# 150224_AriloRX_REV2_0_0_V2.net
KiCad netlist of a schematic drawn in EAGLE
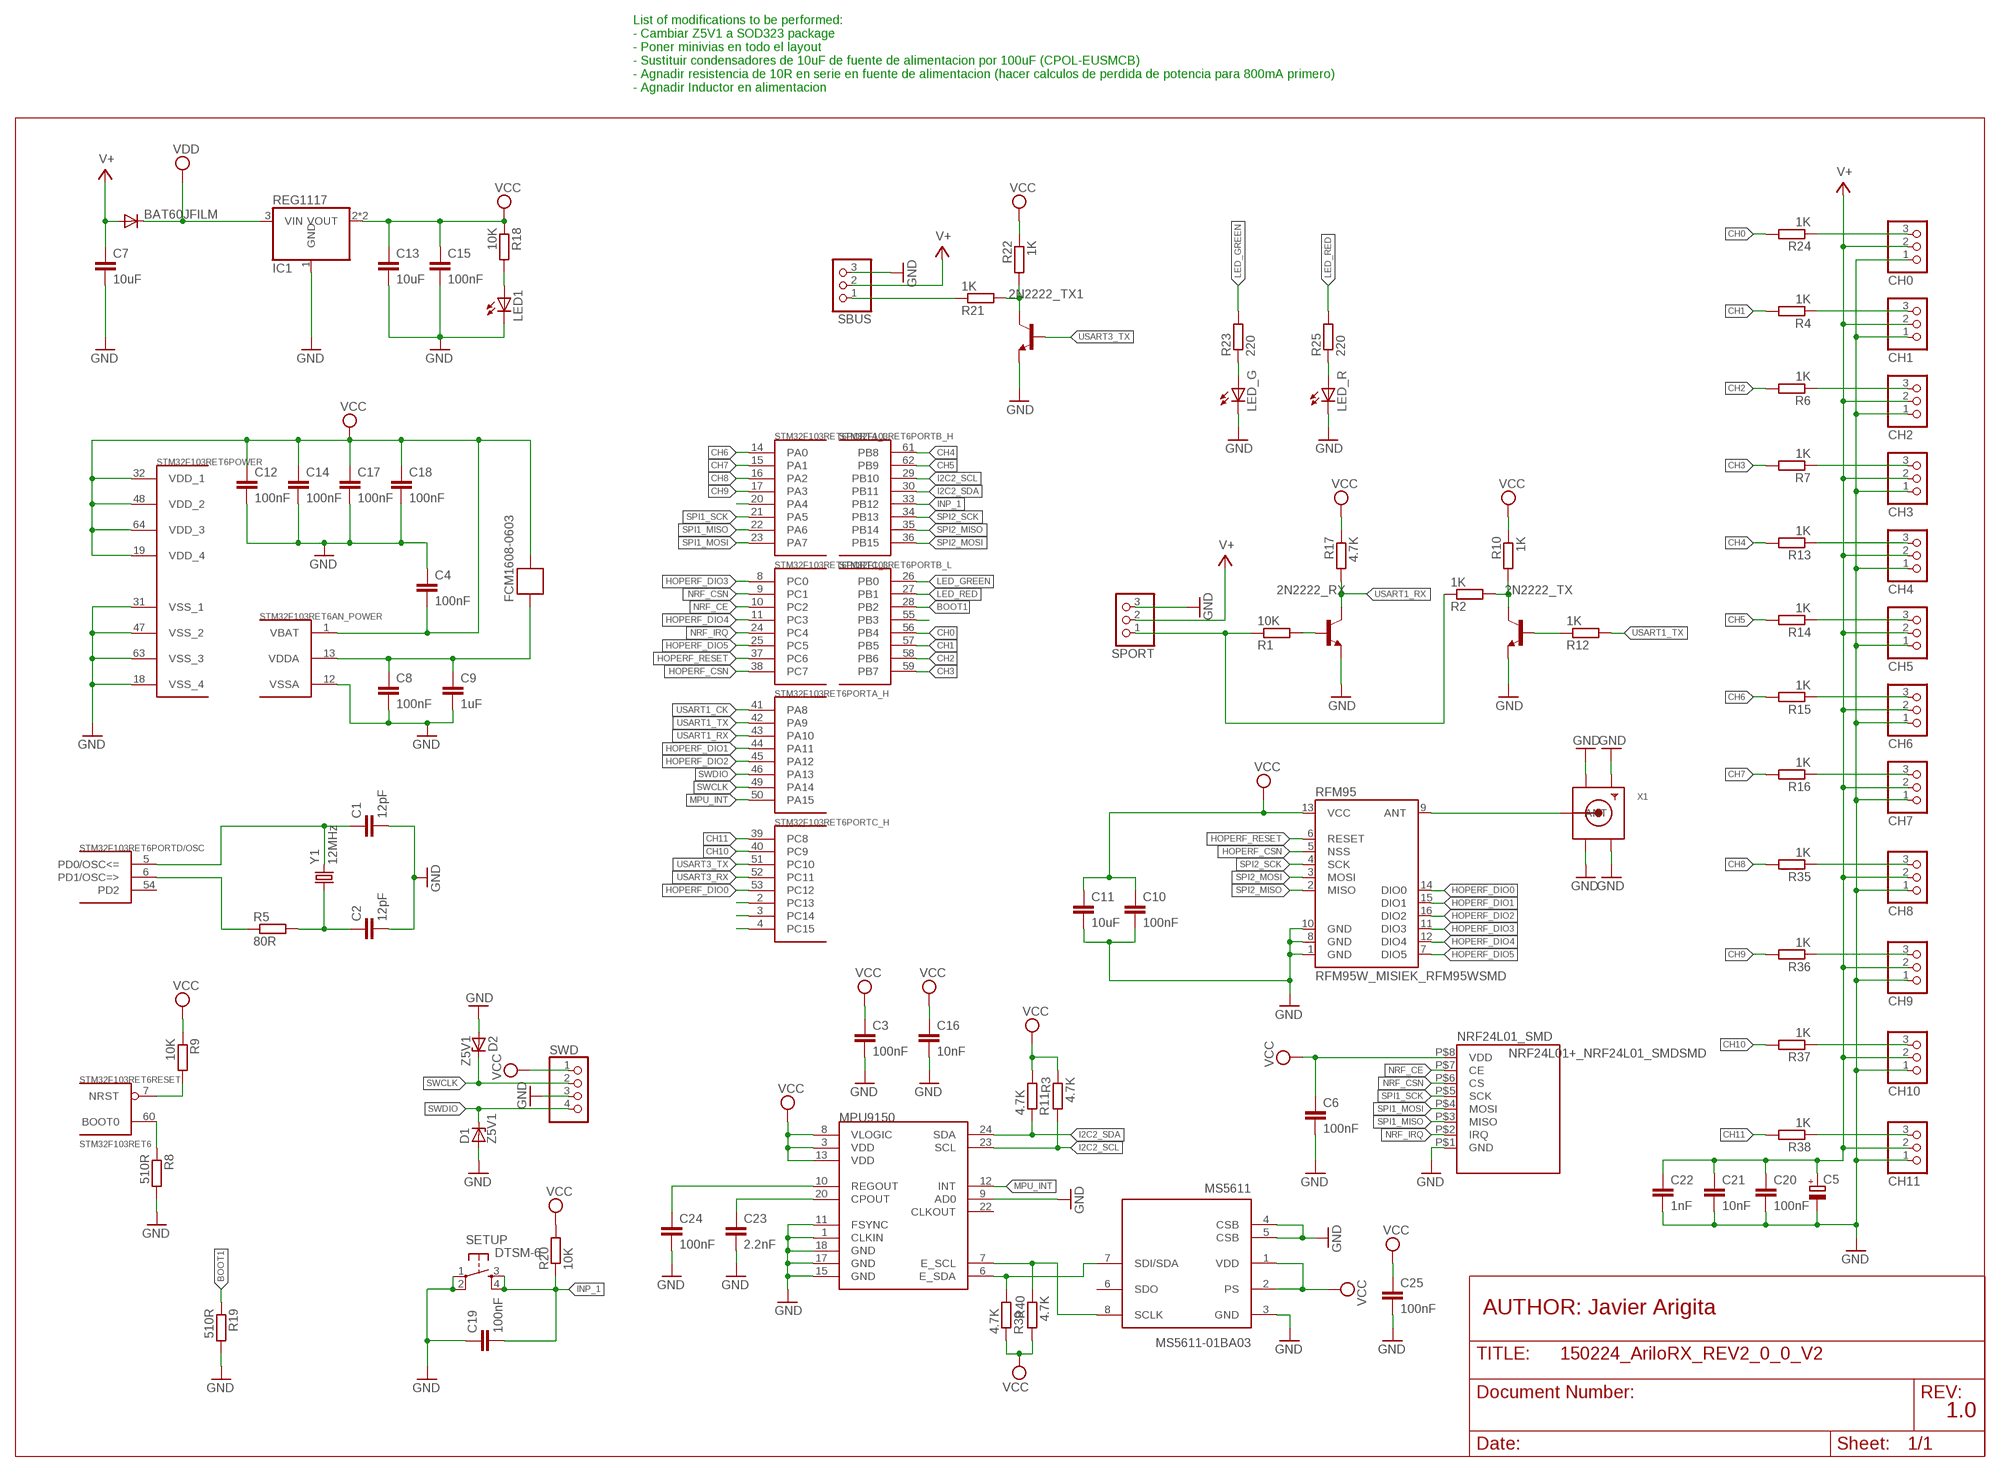
[diagram p0: schematic, sheet 1]

(export (version "E")
  (design (tool "Eeschema 10.0.6"))
  (components
    (comp (ref "2N2222_RX")
      (value "MMBT2222ALT1-NPN-SOT23-BEC")
      (footprint "eagle-import:SOT23-BEC")
      (libsource (lib "eagle-import") (part "-NPN-SOT23-BECMMBT2222ALT1"))
    )
    (comp (ref "2N2222_TX")
      (value "MMBT2222ALT1-NPN-SOT23-BEC")
      (footprint "eagle-import:SOT23-BEC")
      (libsource (lib "eagle-import") (part "-NPN-SOT23-BECMMBT2222ALT1"))
    )
    (comp (ref "2N2222_TX1")
      (value "MMBT2222ALT1-NPN-SOT23-BEC")
      (footprint "eagle-import:SOT23-BEC")
      (libsource (lib "eagle-import") (part "-NPN-SOT23-BECMMBT2222ALT1"))
    )
    (comp (ref "BAT60JFILM")
      (value "DIODE-SOD323-R")
      (footprint "eagle-import:SOD323-R")
      (libsource (lib "eagle-import") (part "DIODE-SOD323-R"))
    )
    (comp (ref "C1")
      (value "12pF")
      (footprint "eagle-import:RESISTOR_C0603")
      (libsource (lib "eagle-import") (part "RESISTOR_C-EUC0603"))
    )
    (comp (ref "C2")
      (value "12pF")
      (footprint "eagle-import:RESISTOR_C0603")
      (libsource (lib "eagle-import") (part "RESISTOR_C-EUC0603"))
    )
    (comp (ref "C3")
      (value "100nF")
      (footprint "eagle-import:RESISTOR_C0603")
      (libsource (lib "eagle-import") (part "RESISTOR_C-EUC0603"))
    )
    (comp (ref "C4")
      (value "100nF")
      (footprint "eagle-import:RESISTOR_C0603")
      (libsource (lib "eagle-import") (part "RESISTOR_C-EUC0603"))
    )
    (comp (ref "C5")
      (value "CPOL-EUSMCB")
      (footprint "eagle-import:SMC_B")
      (libsource (lib "eagle-import") (part "CPOL-EUSMCB"))
    )
    (comp (ref "C6")
      (value "100nF")
      (footprint "eagle-import:RESISTOR_C0603")
      (libsource (lib "eagle-import") (part "RESISTOR_C-EUC0603"))
    )
    (comp (ref "C7")
      (value "10uF")
      (footprint "eagle-import:RESISTOR_C3216")
      (libsource (lib "eagle-import") (part "RESISTOR_C-EUC3216"))
    )
    (comp (ref "C8")
      (value "100nF")
      (footprint "eagle-import:RESISTOR_C0603")
      (libsource (lib "eagle-import") (part "RESISTOR_C-EUC0603"))
    )
    (comp (ref "C9")
      (value "1uF")
      (footprint "eagle-import:RESISTOR_C0603")
      (libsource (lib "eagle-import") (part "RESISTOR_C-EUC0603"))
    )
    (comp (ref "C10")
      (value "100nF")
      (footprint "eagle-import:RESISTOR_C0603")
      (libsource (lib "eagle-import") (part "RESISTOR_C-EUC0603"))
    )
    (comp (ref "C11")
      (value "10uF")
      (footprint "eagle-import:RESISTOR_C3216")
      (libsource (lib "eagle-import") (part "RESISTOR_C-EUC3216"))
    )
    (comp (ref "C12")
      (value "100nF")
      (footprint "eagle-import:RESISTOR_C0603")
      (libsource (lib "eagle-import") (part "RESISTOR_C-EUC0603"))
    )
    (comp (ref "C13")
      (value "10uF")
      (footprint "eagle-import:RESISTOR_C3216")
      (libsource (lib "eagle-import") (part "RESISTOR_C-EUC3216"))
    )
    (comp (ref "C14")
      (value "100nF")
      (footprint "eagle-import:RESISTOR_C0603")
      (libsource (lib "eagle-import") (part "RESISTOR_C-EUC0603"))
    )
    (comp (ref "C15")
      (value "100nF")
      (footprint "eagle-import:RESISTOR_C0603")
      (libsource (lib "eagle-import") (part "RESISTOR_C-EUC0603"))
    )
    (comp (ref "C16")
      (value "10nF")
      (footprint "eagle-import:RESISTOR_C0603")
      (libsource (lib "eagle-import") (part "RESISTOR_C-EUC0603"))
    )
    (comp (ref "C17")
      (value "100nF")
      (footprint "eagle-import:RESISTOR_C0603")
      (libsource (lib "eagle-import") (part "RESISTOR_C-EUC0603"))
    )
    (comp (ref "C18")
      (value "100nF")
      (footprint "eagle-import:RESISTOR_C0603")
      (libsource (lib "eagle-import") (part "RESISTOR_C-EUC0603"))
    )
    (comp (ref "C19")
      (value "100nF")
      (footprint "eagle-import:RESISTOR_C0603")
      (libsource (lib "eagle-import") (part "RESISTOR_C-EUC0603"))
    )
    (comp (ref "C20")
      (value "100nF")
      (footprint "eagle-import:RESISTOR_C0603")
      (libsource (lib "eagle-import") (part "RESISTOR_C-EUC0603"))
    )
    (comp (ref "C21")
      (value "10nF")
      (footprint "eagle-import:RESISTOR_C0603")
      (libsource (lib "eagle-import") (part "RESISTOR_C-EUC0603"))
    )
    (comp (ref "C22")
      (value "1nF")
      (footprint "eagle-import:RESISTOR_C0603")
      (libsource (lib "eagle-import") (part "RESISTOR_C-EUC0603"))
    )
    (comp (ref "C23")
      (value "2.2nF")
      (footprint "eagle-import:RESISTOR_C0603")
      (libsource (lib "eagle-import") (part "RESISTOR_C-EUC0603"))
    )
    (comp (ref "C24")
      (value "100nF")
      (footprint "eagle-import:RESISTOR_C0603")
      (libsource (lib "eagle-import") (part "RESISTOR_C-EUC0603"))
    )
    (comp (ref "C25")
      (value "100nF")
      (footprint "eagle-import:RESISTOR_C0603")
      (libsource (lib "eagle-import") (part "RESISTOR_C-EUC0603"))
    )
    (comp (ref "CH0")
      (value "PINHD-1X3")
      (footprint "eagle-import:1X03")
      (libsource (lib "eagle-import") (part "PINHD-1X3"))
    )
    (comp (ref "CH1")
      (value "PINHD-1X3")
      (footprint "eagle-import:1X03")
      (libsource (lib "eagle-import") (part "PINHD-1X3"))
    )
    (comp (ref "CH2")
      (value "PINHD-1X3")
      (footprint "eagle-import:1X03")
      (libsource (lib "eagle-import") (part "PINHD-1X3"))
    )
    (comp (ref "CH3")
      (value "PINHD-1X3")
      (footprint "eagle-import:1X03")
      (libsource (lib "eagle-import") (part "PINHD-1X3"))
    )
    (comp (ref "CH4")
      (value "PINHD-1X3")
      (footprint "eagle-import:1X03")
      (libsource (lib "eagle-import") (part "PINHD-1X3"))
    )
    (comp (ref "CH5")
      (value "PINHD-1X3")
      (footprint "eagle-import:1X03")
      (libsource (lib "eagle-import") (part "PINHD-1X3"))
    )
    (comp (ref "CH6")
      (value "PINHD-1X3")
      (footprint "eagle-import:1X03")
      (libsource (lib "eagle-import") (part "PINHD-1X3"))
    )
    (comp (ref "CH7")
      (value "PINHD-1X3")
      (footprint "eagle-import:1X03")
      (libsource (lib "eagle-import") (part "PINHD-1X3"))
    )
    (comp (ref "CH8")
      (value "PINHD-1X3")
      (footprint "eagle-import:1X03")
      (libsource (lib "eagle-import") (part "PINHD-1X3"))
    )
    (comp (ref "CH9")
      (value "PINHD-1X3")
      (footprint "eagle-import:1X03")
      (libsource (lib "eagle-import") (part "PINHD-1X3"))
    )
    (comp (ref "CH10")
      (value "PINHD-1X3")
      (footprint "eagle-import:1X03")
      (libsource (lib "eagle-import") (part "PINHD-1X3"))
    )
    (comp (ref "CH11")
      (value "PINHD-1X3")
      (footprint "eagle-import:1X03")
      (libsource (lib "eagle-import") (part "PINHD-1X3"))
    )
    (comp (ref "D1")
      (value "Z5V1")
      (footprint "eagle-import:SOD80C")
      (libsource (lib "eagle-import") (part "ZENER-DIODESOD80C"))
    )
    (comp (ref "D2")
      (value "Z5V1")
      (footprint "eagle-import:SOD80C")
      (libsource (lib "eagle-import") (part "ZENER-DIODESOD80C"))
    )
    (comp (ref "FCM1608-0603")
      (value "FERRITE-BEAD")
      (footprint "eagle-import:R0603")
      (libsource (lib "eagle-import") (part "FERRITE-BEAD"))
    )
    (comp (ref "IC1")
      (value "REG1117")
      (footprint "eagle-import:SOT223")
      (libsource (lib "eagle-import") (part "REG1117"))
    )
    (comp (ref "LED1")
      (value "LED_LEDCHIP-LED0603")
      (footprint "eagle-import:LED_CHIP-LED0603")
      (libsource (lib "eagle-import") (part "LED_LEDCHIP-LED0603"))
    )
    (comp (ref "LED_G")
      (value "LEDCHIP-LED0603")
      (footprint "eagle-import:CHIP-LED0603")
      (libsource (lib "eagle-import") (part "LEDCHIP-LED0603"))
    )
    (comp (ref "LED_R")
      (value "LEDCHIP-LED0603")
      (footprint "eagle-import:CHIP-LED0603")
      (libsource (lib "eagle-import") (part "LEDCHIP-LED0603"))
    )
    (comp (ref "MPU9150")
      (value "MPU-9150QFN-24-NP")
      (footprint "eagle-import:QFN-24-NP")
      (libsource (lib "eagle-import") (part "MPU-9150QFN-24-NP"))
    )
    (comp (ref "MS5611")
      (value "MS5611-01BA03")
      (footprint "eagle-import:SON125P300X500X100-8N")
      (libsource (lib "eagle-import") (part "MS5611-01BA03"))
    )
    (comp (ref "NRF24L01_SMD")
      (value "NRF24L01+_NRF24L01_SMDSMD")
      (footprint "eagle-import:NRF24L01+_NRF24L01_SMD")
      (libsource (lib "eagle-import") (part "NRF24L01+_NRF24L01_SMDSMD"))
    )
    (comp (ref "R1")
      (value "10K")
      (footprint "eagle-import:RCL_R0603")
      (libsource (lib "eagle-import") (part "RCL_R-EU_R0603"))
    )
    (comp (ref "R2")
      (value "1K")
      (footprint "eagle-import:RCL_R0603")
      (libsource (lib "eagle-import") (part "RCL_R-EU_R0603"))
    )
    (comp (ref "R3")
      (value "4.7K")
      (footprint "eagle-import:RCL_R0603")
      (libsource (lib "eagle-import") (part "RCL_R-EU_R0603"))
    )
    (comp (ref "R4")
      (value "1K")
      (footprint "eagle-import:RCL_R0603")
      (libsource (lib "eagle-import") (part "RCL_R-EU_R0603"))
    )
    (comp (ref "R5")
      (value "80R")
      (footprint "eagle-import:RCL_R0603")
      (libsource (lib "eagle-import") (part "RCL_R-EU_R0603"))
    )
    (comp (ref "R6")
      (value "1K")
      (footprint "eagle-import:RCL_R0603")
      (libsource (lib "eagle-import") (part "RCL_R-EU_R0603"))
    )
    (comp (ref "R7")
      (value "1K")
      (footprint "eagle-import:RCL_R0603")
      (libsource (lib "eagle-import") (part "RCL_R-EU_R0603"))
    )
    (comp (ref "R8")
      (value "510R")
      (footprint "eagle-import:RCL_R0603")
      (libsource (lib "eagle-import") (part "RCL_R-EU_R0603"))
    )
    (comp (ref "R9")
      (value "10K")
      (footprint "eagle-import:RCL_R0603")
      (libsource (lib "eagle-import") (part "RCL_R-EU_R0603"))
    )
    (comp (ref "R10")
      (value "1K")
      (footprint "eagle-import:RCL_R0603")
      (libsource (lib "eagle-import") (part "RCL_R-EU_R0603"))
    )
    (comp (ref "R11")
      (value "4.7K")
      (footprint "eagle-import:RCL_R0603")
      (libsource (lib "eagle-import") (part "RCL_R-EU_R0603"))
    )
    (comp (ref "R12")
      (value "1K")
      (footprint "eagle-import:RCL_R0603")
      (libsource (lib "eagle-import") (part "RCL_R-EU_R0603"))
    )
    (comp (ref "R13")
      (value "1K")
      (footprint "eagle-import:RCL_R0603")
      (libsource (lib "eagle-import") (part "RCL_R-EU_R0603"))
    )
    (comp (ref "R14")
      (value "1K")
      (footprint "eagle-import:RCL_R0603")
      (libsource (lib "eagle-import") (part "RCL_R-EU_R0603"))
    )
    (comp (ref "R15")
      (value "1K")
      (footprint "eagle-import:RCL_R0603")
      (libsource (lib "eagle-import") (part "RCL_R-EU_R0603"))
    )
    (comp (ref "R16")
      (value "1K")
      (footprint "eagle-import:RCL_R0603")
      (libsource (lib "eagle-import") (part "RCL_R-EU_R0603"))
    )
    (comp (ref "R17")
      (value "4.7K")
      (footprint "eagle-import:RCL_R0603")
      (libsource (lib "eagle-import") (part "RCL_R-EU_R0603"))
    )
    (comp (ref "R18")
      (value "10K")
      (footprint "eagle-import:RCL_R0603")
      (libsource (lib "eagle-import") (part "RCL_R-EU_R0603"))
    )
    (comp (ref "R19")
      (value "510R")
      (footprint "eagle-import:RCL_R0603")
      (libsource (lib "eagle-import") (part "RCL_R-EU_R0603"))
    )
    (comp (ref "R20")
      (value "10K")
      (footprint "eagle-import:RCL_R0603")
      (libsource (lib "eagle-import") (part "RCL_R-EU_R0603"))
    )
    (comp (ref "R21")
      (value "1K")
      (footprint "eagle-import:RCL_R0603")
      (libsource (lib "eagle-import") (part "RCL_R-EU_R0603"))
    )
    (comp (ref "R22")
      (value "1K")
      (footprint "eagle-import:RCL_R0603")
      (libsource (lib "eagle-import") (part "RCL_R-EU_R0603"))
    )
    (comp (ref "R23")
      (value "220")
      (footprint "eagle-import:RCL_R0603")
      (libsource (lib "eagle-import") (part "RCL_R-EU_R0603"))
    )
    (comp (ref "R24")
      (value "1K")
      (footprint "eagle-import:RCL_R0603")
      (libsource (lib "eagle-import") (part "RCL_R-EU_R0603"))
    )
    (comp (ref "R25")
      (value "220")
      (footprint "eagle-import:RCL_R0603")
      (libsource (lib "eagle-import") (part "RCL_R-EU_R0603"))
    )
    (comp (ref "R35")
      (value "1K")
      (footprint "eagle-import:RCL_R0603")
      (libsource (lib "eagle-import") (part "RCL_R-EU_R0603"))
    )
    (comp (ref "R36")
      (value "1K")
      (footprint "eagle-import:RCL_R0603")
      (libsource (lib "eagle-import") (part "RCL_R-EU_R0603"))
    )
    (comp (ref "R37")
      (value "1K")
      (footprint "eagle-import:RCL_R0603")
      (libsource (lib "eagle-import") (part "RCL_R-EU_R0603"))
    )
    (comp (ref "R38")
      (value "1K")
      (footprint "eagle-import:RCL_R0603")
      (libsource (lib "eagle-import") (part "RCL_R-EU_R0603"))
    )
    (comp (ref "R39")
      (value "4.7K")
      (footprint "eagle-import:RCL_R0603")
      (libsource (lib "eagle-import") (part "RCL_R-EU_R0603"))
    )
    (comp (ref "R40")
      (value "4.7K")
      (footprint "eagle-import:RCL_R0603")
      (libsource (lib "eagle-import") (part "RCL_R-EU_R0603"))
    )
    (comp (ref "RFM95")
      (value "RFM95W_MISIEK_RFM95WSMD")
      (footprint "eagle-import:RFM95W_MISIEK_RFM95W_SMD")
      (libsource (lib "eagle-import") (part "RFM95W_MISIEK_RFM95WSMD"))
    )
    (comp (ref "SBUS")
      (value "PINHD-1X3")
      (footprint "eagle-import:1X03")
      (libsource (lib "eagle-import") (part "PINHD-1X3"))
    )
    (comp (ref "SETUP")
      (value "DTSM-6")
      (footprint "eagle-import:DTSM-6")
      (libsource (lib "eagle-import") (part "DTSM-6"))
    )
    (comp (ref "SPORT")
      (value "PINHD-1X3")
      (footprint "eagle-import:1X03")
      (libsource (lib "eagle-import") (part "PINHD-1X3"))
    )
    (comp (ref "STM32F103RET6")
      (value "STM32F103RET6")
      (footprint "eagle-import:TQFP64")
      (libsource (lib "eagle-import") (part "STM32F10XRXT6"))
    )
    (comp (ref "SWD")
      (value "PINHD-1X4")
      (footprint "eagle-import:1X04")
      (libsource (lib "eagle-import") (part "PINHD-1X4"))
    )
    (comp (ref "X1")
      (value "SMACONNECTOR_EDGE")
      (footprint "eagle-import:SMA_EDGELAUNCH")
      (libsource (lib "eagle-import") (part "SMACONNECTOR_EDGE"))
    )
    (comp (ref "Y1")
      (value "12MHz")
      (footprint "eagle-import:CRYSTAL-SMD-5X3")
      (libsource (lib "eagle-import") (part "CRYSTAL5X3"))
    )
  )
  (nets
    (net (code "1") (name "BOOT1") (class "Default")
      (node (ref "R19") (pin "1") (pinfunction "1_1") (pintype "passive"))
      (node (ref "STM32F103RET6") (pin "28") (pinfunction "PB2_28") (pintype "bidirectional"))
    )
    (net (code "2") (name "CH0") (class "Default")
      (node (ref "R24") (pin "2") (pinfunction "2_2") (pintype "passive"))
      (node (ref "STM32F103RET6") (pin "56") (pinfunction "PB4_56") (pintype "bidirectional"))
    )
    (net (code "3") (name "CH1") (class "Default")
      (node (ref "R4") (pin "2") (pinfunction "2_2") (pintype "passive"))
      (node (ref "STM32F103RET6") (pin "57") (pinfunction "PB5_57") (pintype "bidirectional"))
    )
    (net (code "4") (name "CH2") (class "Default")
      (node (ref "R6") (pin "2") (pinfunction "2_2") (pintype "passive"))
      (node (ref "STM32F103RET6") (pin "58") (pinfunction "PB6_58") (pintype "bidirectional"))
    )
    (net (code "5") (name "CH3") (class "Default")
      (node (ref "R7") (pin "2") (pinfunction "2_2") (pintype "passive"))
      (node (ref "STM32F103RET6") (pin "59") (pinfunction "PB7_59") (pintype "bidirectional"))
    )
    (net (code "6") (name "CH4") (class "Default")
      (node (ref "R13") (pin "2") (pinfunction "2_2") (pintype "passive"))
      (node (ref "STM32F103RET6") (pin "61") (pinfunction "PB8_61") (pintype "bidirectional"))
    )
    (net (code "7") (name "CH5") (class "Default")
      (node (ref "R14") (pin "2") (pinfunction "2_2") (pintype "passive"))
      (node (ref "STM32F103RET6") (pin "62") (pinfunction "PB9_62") (pintype "bidirectional"))
    )
    (net (code "8") (name "CH6") (class "Default")
      (node (ref "R15") (pin "2") (pinfunction "2_2") (pintype "passive"))
      (node (ref "STM32F103RET6") (pin "14") (pinfunction "PA0_14") (pintype "bidirectional"))
    )
    (net (code "9") (name "CH7") (class "Default")
      (node (ref "R16") (pin "2") (pinfunction "2_2") (pintype "passive"))
      (node (ref "STM32F103RET6") (pin "15") (pinfunction "PA1_15") (pintype "bidirectional"))
    )
    (net (code "10") (name "CH8") (class "Default")
      (node (ref "R35") (pin "2") (pinfunction "2_2") (pintype "passive"))
      (node (ref "STM32F103RET6") (pin "16") (pinfunction "PA2_16") (pintype "bidirectional"))
    )
    (net (code "11") (name "CH9") (class "Default")
      (node (ref "R36") (pin "2") (pinfunction "2_2") (pintype "passive"))
      (node (ref "STM32F103RET6") (pin "17") (pinfunction "PA3_17") (pintype "bidirectional"))
    )
    (net (code "12") (name "CH10") (class "Default")
      (node (ref "R37") (pin "2") (pinfunction "2_2") (pintype "passive"))
      (node (ref "STM32F103RET6") (pin "40") (pinfunction "PC9_40") (pintype "bidirectional"))
    )
    (net (code "13") (name "CH11") (class "Default")
      (node (ref "R38") (pin "2") (pinfunction "2_2") (pintype "passive"))
      (node (ref "STM32F103RET6") (pin "39") (pinfunction "PC8_39") (pintype "bidirectional"))
    )
    (net (code "14") (name "GND") (class "Default")
      (node (ref "2N2222_RX") (pin "E") (pinfunction "E_E") (pintype "passive"))
      (node (ref "2N2222_TX") (pin "E") (pinfunction "E_E") (pintype "passive"))
      (node (ref "2N2222_TX1") (pin "E") (pinfunction "E_E") (pintype "passive"))
      (node (ref "C1") (pin "2") (pinfunction "2_2") (pintype "passive"))
      (node (ref "C10") (pin "2") (pinfunction "2_2") (pintype "passive"))
      (node (ref "C11") (pin "2") (pinfunction "2_2") (pintype "passive"))
      (node (ref "C12") (pin "2") (pinfunction "2_2") (pintype "passive"))
      (node (ref "C13") (pin "2") (pinfunction "2_2") (pintype "passive"))
      (node (ref "C14") (pin "2") (pinfunction "2_2") (pintype "passive"))
      (node (ref "C15") (pin "2") (pinfunction "2_2") (pintype "passive"))
      (node (ref "C16") (pin "2") (pinfunction "2_2") (pintype "passive"))
      (node (ref "C17") (pin "2") (pinfunction "2_2") (pintype "passive"))
      (node (ref "C18") (pin "2") (pinfunction "2_2") (pintype "passive"))
      (node (ref "C19") (pin "1") (pinfunction "1_1") (pintype "passive"))
      (node (ref "C2") (pin "2") (pinfunction "2_2") (pintype "passive"))
      (node (ref "C20") (pin "2") (pinfunction "2_2") (pintype "passive"))
      (node (ref "C21") (pin "2") (pinfunction "2_2") (pintype "passive"))
      (node (ref "C22") (pin "2") (pinfunction "2_2") (pintype "passive"))
      (node (ref "C23") (pin "2") (pinfunction "2_2") (pintype "passive"))
      (node (ref "C24") (pin "2") (pinfunction "2_2") (pintype "passive"))
      (node (ref "C25") (pin "2") (pinfunction "2_2") (pintype "passive"))
      (node (ref "C3") (pin "2") (pinfunction "2_2") (pintype "passive"))
      (node (ref "C4") (pin "1") (pinfunction "1_1") (pintype "passive"))
      (node (ref "C5") (pin "-") (pinfunction "-_-") (pintype "passive"))
      (node (ref "C6") (pin "2") (pinfunction "2_2") (pintype "passive"))
      (node (ref "C7") (pin "2") (pinfunction "2_2") (pintype "passive"))
      (node (ref "C8") (pin "2") (pinfunction "2_2") (pintype "passive"))
      (node (ref "C9") (pin "2") (pinfunction "2_2") (pintype "passive"))
      (node (ref "CH0") (pin "1") (pinfunction "1_1") (pintype "passive"))
      (node (ref "CH1") (pin "1") (pinfunction "1_1") (pintype "passive"))
      (node (ref "CH10") (pin "1") (pinfunction "1_1") (pintype "passive"))
      (node (ref "CH11") (pin "1") (pinfunction "1_1") (pintype "passive"))
      (node (ref "CH2") (pin "1") (pinfunction "1_1") (pintype "passive"))
      (node (ref "CH3") (pin "1") (pinfunction "1_1") (pintype "passive"))
      (node (ref "CH4") (pin "1") (pinfunction "1_1") (pintype "passive"))
      (node (ref "CH5") (pin "1") (pinfunction "1_1") (pintype "passive"))
      (node (ref "CH6") (pin "1") (pinfunction "1_1") (pintype "passive"))
      (node (ref "CH7") (pin "1") (pinfunction "1_1") (pintype "passive"))
      (node (ref "CH8") (pin "1") (pinfunction "1_1") (pintype "passive"))
      (node (ref "CH9") (pin "1") (pinfunction "1_1") (pintype "passive"))
      (node (ref "D1") (pin "A") (pinfunction "A_A") (pintype "passive"))
      (node (ref "D2") (pin "A") (pinfunction "A_A") (pintype "passive"))
      (node (ref "IC1") (pin "1") (pinfunction "GND_1") (pintype "power_in"))
      (node (ref "LED1") (pin "C") (pinfunction "C_C") (pintype "passive"))
      (node (ref "LED_G") (pin "C") (pinfunction "C_C") (pintype "passive"))
      (node (ref "LED_R") (pin "C") (pinfunction "C_C") (pintype "passive"))
      (node (ref "MPU9150") (pin "1") (pinfunction "CLKIN_1") (pintype "bidirectional"))
      (node (ref "MPU9150") (pin "11") (pinfunction "FSYNC_11") (pintype "bidirectional"))
      (node (ref "MPU9150") (pin "15") (pinfunction "GND_15") (pintype "bidirectional"))
      (node (ref "MPU9150") (pin "17") (pinfunction "GND_17") (pintype "bidirectional"))
      (node (ref "MPU9150") (pin "18") (pinfunction "GND_18") (pintype "bidirectional"))
      (node (ref "MPU9150") (pin "9") (pinfunction "AD0_9") (pintype "bidirectional"))
      (node (ref "MS5611") (pin "3") (pinfunction "GND_3") (pintype "power_in"))
      (node (ref "MS5611") (pin "4") (pinfunction "CSB_4") (pintype "input"))
      (node (ref "MS5611") (pin "5") (pinfunction "CSB_5") (pintype "input"))
      (node (ref "NRF24L01_SMD") (pin "P$1") (pinfunction "GND_P$1") (pintype "power_in"))
      (node (ref "R19") (pin "2") (pinfunction "2_2") (pintype "passive"))
      (node (ref "R8") (pin "2") (pinfunction "2_2") (pintype "passive"))
      (node (ref "RFM95") (pin "1") (pinfunction "GND_1") (pintype "power_in"))
      (node (ref "RFM95") (pin "10") (pinfunction "GND_10") (pintype "power_in"))
      (node (ref "RFM95") (pin "8") (pinfunction "GND_8") (pintype "power_in"))
      (node (ref "SBUS") (pin "3") (pinfunction "3_3") (pintype "passive"))
      (node (ref "SETUP") (pin "1") (pinfunction "1_1") (pintype "passive"))
      (node (ref "SETUP") (pin "2") (pinfunction "2_2") (pintype "passive"))
      (node (ref "SPORT") (pin "3") (pinfunction "3_3") (pintype "passive"))
      (node (ref "STM32F103RET6") (pin "12") (pinfunction "VSSA_12") (pintype "power_in"))
      (node (ref "STM32F103RET6") (pin "18") (pinfunction "VSS_4_18") (pintype "power_in"))
      (node (ref "STM32F103RET6") (pin "31") (pinfunction "VSS_1_31") (pintype "power_in"))
      (node (ref "STM32F103RET6") (pin "47") (pinfunction "VSS_2_47") (pintype "power_in"))
      (node (ref "STM32F103RET6") (pin "63") (pinfunction "VSS_3_63") (pintype "power_in"))
      (node (ref "SWD") (pin "3") (pinfunction "3_3") (pintype "passive"))
      (node (ref "X1") (pin "GND@1") (pinfunction "GND4_GND@1") (pintype "power_in"))
      (node (ref "X1") (pin "GND@2") (pinfunction "GND3_GND@2") (pintype "power_in"))
      (node (ref "X1") (pin "GND@3") (pinfunction "GND2_GND@3") (pintype "power_in"))
      (node (ref "X1") (pin "GND@4") (pinfunction "GND1_GND@4") (pintype "power_in"))
    )
    (net (code "15") (name "HOPERF_CSN") (class "Default")
      (node (ref "RFM95") (pin "5") (pinfunction "NSS_5") (pintype "input"))
      (node (ref "STM32F103RET6") (pin "38") (pinfunction "PC7_38") (pintype "bidirectional"))
    )
    (net (code "16") (name "HOPERF_DIO0") (class "Default")
      (node (ref "RFM95") (pin "14") (pinfunction "DIO0_14") (pintype "input"))
      (node (ref "STM32F103RET6") (pin "53") (pinfunction "PC12_53") (pintype "bidirectional"))
    )
    (net (code "17") (name "HOPERF_DIO1") (class "Default")
      (node (ref "RFM95") (pin "15") (pinfunction "DIO1_15") (pintype "input"))
      (node (ref "STM32F103RET6") (pin "44") (pinfunction "PA11_44") (pintype "bidirectional"))
    )
    (net (code "18") (name "HOPERF_DIO2") (class "Default")
      (node (ref "RFM95") (pin "16") (pinfunction "DIO2_16") (pintype "input"))
      (node (ref "STM32F103RET6") (pin "45") (pinfunction "PA12_45") (pintype "bidirectional"))
    )
    (net (code "19") (name "HOPERF_DIO3") (class "Default")
      (node (ref "RFM95") (pin "11") (pinfunction "DIO3_11") (pintype "bidirectional"))
      (node (ref "STM32F103RET6") (pin "8") (pinfunction "PC0_8") (pintype "bidirectional"))
    )
    (net (code "20") (name "HOPERF_DIO4") (class "Default")
      (node (ref "RFM95") (pin "12") (pinfunction "DIO4_12") (pintype "bidirectional"))
      (node (ref "STM32F103RET6") (pin "11") (pinfunction "PC3_11") (pintype "bidirectional"))
    )
    (net (code "21") (name "HOPERF_DIO5") (class "Default")
      (node (ref "RFM95") (pin "7") (pinfunction "DIO5_7") (pintype "bidirectional"))
      (node (ref "STM32F103RET6") (pin "25") (pinfunction "PC5_25") (pintype "bidirectional"))
    )
    (net (code "22") (name "HOPERF_RESET") (class "Default")
      (node (ref "RFM95") (pin "6") (pinfunction "RESET_6") (pintype "output"))
      (node (ref "STM32F103RET6") (pin "37") (pinfunction "PC6_37") (pintype "bidirectional"))
    )
    (net (code "23") (name "I2C2_SCL") (class "Default")
      (node (ref "MPU9150") (pin "23") (pinfunction "SCL_23") (pintype "bidirectional"))
      (node (ref "R3") (pin "2") (pinfunction "2_2") (pintype "passive"))
      (node (ref "STM32F103RET6") (pin "29") (pinfunction "PB10_29") (pintype "bidirectional"))
    )
    (net (code "24") (name "I2C2_SDA") (class "Default")
      (node (ref "MPU9150") (pin "24") (pinfunction "SDA_24") (pintype "bidirectional"))
      (node (ref "R11") (pin "1") (pinfunction "1_1") (pintype "passive"))
      (node (ref "STM32F103RET6") (pin "30") (pinfunction "PB11_30") (pintype "bidirectional"))
    )
    (net (code "25") (name "INP_1") (class "Default")
      (node (ref "C19") (pin "2") (pinfunction "2_2") (pintype "passive"))
      (node (ref "R20") (pin "1") (pinfunction "1_1") (pintype "passive"))
      (node (ref "SETUP") (pin "3") (pinfunction "3_3") (pintype "passive"))
      (node (ref "SETUP") (pin "4") (pinfunction "4_4") (pintype "passive"))
      (node (ref "STM32F103RET6") (pin "33") (pinfunction "PB12_33") (pintype "bidirectional"))
    )
    (net (code "26") (name "LED_GREEN") (class "Default")
      (node (ref "R23") (pin "2") (pinfunction "2_2") (pintype "passive"))
      (node (ref "STM32F103RET6") (pin "26") (pinfunction "PB0_26") (pintype "bidirectional"))
    )
    (net (code "27") (name "LED_RED") (class "Default")
      (node (ref "R25") (pin "2") (pinfunction "2_2") (pintype "passive"))
      (node (ref "STM32F103RET6") (pin "27") (pinfunction "PB1_27") (pintype "bidirectional"))
    )
    (net (code "28") (name "MPU_INT") (class "Default")
      (node (ref "MPU9150") (pin "12") (pinfunction "INT_12") (pintype "bidirectional"))
      (node (ref "STM32F103RET6") (pin "50") (pinfunction "PA15_50") (pintype "bidirectional"))
    )
    (net (code "29") (name "NRF_CE") (class "Default")
      (node (ref "NRF24L01_SMD") (pin "P$7") (pinfunction "CE_P$7") (pintype "input"))
      (node (ref "STM32F103RET6") (pin "10") (pinfunction "PC2_10") (pintype "bidirectional"))
    )
    (net (code "30") (name "NRF_CSN") (class "Default")
      (node (ref "NRF24L01_SMD") (pin "P$6") (pinfunction "CS_P$6") (pintype "input"))
      (node (ref "STM32F103RET6") (pin "9") (pinfunction "PC1_9") (pintype "bidirectional"))
    )
    (net (code "31") (name "NRF_IRQ") (class "Default")
      (node (ref "NRF24L01_SMD") (pin "P$2") (pinfunction "IRQ_P$2") (pintype "output"))
      (node (ref "STM32F103RET6") (pin "24") (pinfunction "PC4_24") (pintype "bidirectional"))
    )
    (net (code "32") (name "Net-(2N2222_RX-PadB)") (class "Default")
      (node (ref "2N2222_RX") (pin "B") (pinfunction "B_B") (pintype "passive"))
      (node (ref "R1") (pin "2") (pinfunction "2_2") (pintype "passive"))
    )
    (net (code "33") (name "Net-(2N2222_TX-PadB)") (class "Default")
      (node (ref "2N2222_TX") (pin "B") (pinfunction "B_B") (pintype "passive"))
      (node (ref "R12") (pin "1") (pinfunction "1_1") (pintype "passive"))
    )
    (net (code "34") (name "Net-(2N2222_TX-PadC)") (class "Default")
      (node (ref "2N2222_TX") (pin "C") (pinfunction "C_C") (pintype "passive"))
      (node (ref "R10") (pin "2") (pinfunction "2_2") (pintype "passive"))
      (node (ref "R2") (pin "2") (pinfunction "2_2") (pintype "passive"))
    )
    (net (code "35") (name "Net-(2N2222_TX1-PadC)") (class "Default")
      (node (ref "2N2222_TX1") (pin "C") (pinfunction "C_C") (pintype "passive"))
      (node (ref "R21") (pin "2") (pinfunction "2_2") (pintype "passive"))
      (node (ref "R22") (pin "2") (pinfunction "2_2") (pintype "passive"))
    )
    (net (code "36") (name "Net-(C2-Pad1)") (class "Default")
      (node (ref "C2") (pin "1") (pinfunction "1_1") (pintype "passive"))
      (node (ref "R5") (pin "2") (pinfunction "2_2") (pintype "passive"))
      (node (ref "Y1") (pin "1") (pinfunction "1_1") (pintype "passive"))
    )
    (net (code "37") (name "Net-(CH0-Pad3)") (class "Default")
      (node (ref "CH0") (pin "3") (pinfunction "3_3") (pintype "passive"))
      (node (ref "R24") (pin "1") (pinfunction "1_1") (pintype "passive"))
    )
    (net (code "38") (name "Net-(CH1-Pad3)") (class "Default")
      (node (ref "CH1") (pin "3") (pinfunction "3_3") (pintype "passive"))
      (node (ref "R4") (pin "1") (pinfunction "1_1") (pintype "passive"))
    )
    (net (code "39") (name "Net-(CH2-Pad3)") (class "Default")
      (node (ref "CH2") (pin "3") (pinfunction "3_3") (pintype "passive"))
      (node (ref "R6") (pin "1") (pinfunction "1_1") (pintype "passive"))
    )
    (net (code "40") (name "Net-(CH3-Pad3)") (class "Default")
      (node (ref "CH3") (pin "3") (pinfunction "3_3") (pintype "passive"))
      (node (ref "R7") (pin "1") (pinfunction "1_1") (pintype "passive"))
    )
    (net (code "41") (name "Net-(CH4-Pad3)") (class "Default")
      (node (ref "CH4") (pin "3") (pinfunction "3_3") (pintype "passive"))
      (node (ref "R13") (pin "1") (pinfunction "1_1") (pintype "passive"))
    )
    (net (code "42") (name "Net-(CH5-Pad3)") (class "Default")
      (node (ref "CH5") (pin "3") (pinfunction "3_3") (pintype "passive"))
      (node (ref "R14") (pin "1") (pinfunction "1_1") (pintype "passive"))
    )
    (net (code "43") (name "Net-(CH6-Pad3)") (class "Default")
      (node (ref "CH6") (pin "3") (pinfunction "3_3") (pintype "passive"))
      (node (ref "R15") (pin "1") (pinfunction "1_1") (pintype "passive"))
    )
    (net (code "44") (name "Net-(CH7-Pad3)") (class "Default")
      (node (ref "CH7") (pin "3") (pinfunction "3_3") (pintype "passive"))
      (node (ref "R16") (pin "1") (pinfunction "1_1") (pintype "passive"))
    )
    (net (code "45") (name "Net-(CH8-Pad3)") (class "Default")
      (node (ref "CH8") (pin "3") (pinfunction "3_3") (pintype "passive"))
      (node (ref "R35") (pin "1") (pinfunction "1_1") (pintype "passive"))
    )
    (net (code "46") (name "Net-(CH9-Pad3)") (class "Default")
      (node (ref "CH9") (pin "3") (pinfunction "3_3") (pintype "passive"))
      (node (ref "R36") (pin "1") (pinfunction "1_1") (pintype "passive"))
    )
    (net (code "47") (name "Net-(CH10-Pad3)") (class "Default")
      (node (ref "CH10") (pin "3") (pinfunction "3_3") (pintype "passive"))
      (node (ref "R37") (pin "1") (pinfunction "1_1") (pintype "passive"))
    )
    (net (code "48") (name "Net-(CH11-Pad3)") (class "Default")
      (node (ref "CH11") (pin "3") (pinfunction "3_3") (pintype "passive"))
      (node (ref "R38") (pin "1") (pinfunction "1_1") (pintype "passive"))
    )
    (net (code "49") (name "Net-(FCM1608-0603-P$2)") (class "Default")
      (node (ref "C8") (pin "1") (pinfunction "1_1") (pintype "passive"))
      (node (ref "C9") (pin "1") (pinfunction "1_1") (pintype "passive"))
      (node (ref "FCM1608-0603") (pin "2") (pinfunction "P$2_2") (pintype "bidirectional"))
      (node (ref "STM32F103RET6") (pin "13") (pinfunction "VDDA_13") (pintype "power_in"))
    )
    (net (code "50") (name "Net-(LED1-PadA)") (class "Default")
      (node (ref "LED1") (pin "A") (pinfunction "A_A") (pintype "passive"))
      (node (ref "R18") (pin "2") (pinfunction "2_2") (pintype "passive"))
    )
    (net (code "51") (name "Net-(LED_G-PadA)") (class "Default")
      (node (ref "LED_G") (pin "A") (pinfunction "A_A") (pintype "passive"))
      (node (ref "R23") (pin "1") (pinfunction "1_1") (pintype "passive"))
    )
    (net (code "52") (name "Net-(LED_R-PadA)") (class "Default")
      (node (ref "LED_R") (pin "A") (pinfunction "A_A") (pintype "passive"))
      (node (ref "R25") (pin "1") (pinfunction "1_1") (pintype "passive"))
    )
    (net (code "53") (name "Net-(MPU9150-CPOUT)") (class "Default")
      (node (ref "C23") (pin "1") (pinfunction "1_1") (pintype "passive"))
      (node (ref "MPU9150") (pin "20") (pinfunction "CPOUT_20") (pintype "bidirectional"))
    )
    (net (code "54") (name "Net-(MPU9150-E_SCL)") (class "Default")
      (node (ref "MPU9150") (pin "7") (pinfunction "E_SCL_7") (pintype "bidirectional"))
      (node (ref "MS5611") (pin "8") (pinfunction "SCLK_8") (pintype "input"))
      (node (ref "R40") (pin "1") (pinfunction "1_1") (pintype "passive"))
    )
    (net (code "55") (name "Net-(MPU9150-E_SDA)") (class "Default")
      (node (ref "MPU9150") (pin "6") (pinfunction "E_SDA_6") (pintype "bidirectional"))
      (node (ref "MS5611") (pin "7") (pinfunction "SDI/SDA_7") (pintype "bidirectional"))
      (node (ref "R39") (pin "2") (pinfunction "2_2") (pintype "passive"))
    )
    (net (code "56") (name "Net-(MPU9150-REGOUT)") (class "Default")
      (node (ref "C24") (pin "1") (pinfunction "1_1") (pintype "passive"))
      (node (ref "MPU9150") (pin "10") (pinfunction "REGOUT_10") (pintype "bidirectional"))
    )
    (net (code "57") (name "Net-(R1-Pad1)") (class "Default")
      (node (ref "R1") (pin "1") (pinfunction "1_1") (pintype "passive"))
      (node (ref "R2") (pin "1") (pinfunction "1_1") (pintype "passive"))
      (node (ref "SPORT") (pin "1") (pinfunction "1_1") (pintype "passive"))
    )
    (net (code "58") (name "Net-(R21-Pad1)") (class "Default")
      (node (ref "R21") (pin "1") (pinfunction "1_1") (pintype "passive"))
      (node (ref "SBUS") (pin "1") (pinfunction "1_1") (pintype "passive"))
    )
    (net (code "59") (name "Net-(RFM95-ANT)") (class "Default")
      (node (ref "RFM95") (pin "9") (pinfunction "ANT_9") (pintype "bidirectional"))
      (node (ref "X1") (pin "P") (pinfunction "ANT_P") (pintype "bidirectional"))
    )
    (net (code "60") (name "Net-(STM32F103RET6H-PD0{slash}OSC<=)") (class "Default")
      (node (ref "C1") (pin "1") (pinfunction "1_1") (pintype "passive"))
      (node (ref "STM32F103RET6") (pin "5") (pinfunction "PD0/OSC<=_5") (pintype "bidirectional"))
      (node (ref "Y1") (pin "3") (pinfunction "2_3") (pintype "passive"))
    )
    (net (code "61") (name "Net-(STM32F103RET6H-PD1{slash}OSC=>)") (class "Default")
      (node (ref "R5") (pin "1") (pinfunction "1_1") (pintype "passive"))
      (node (ref "STM32F103RET6") (pin "6") (pinfunction "PD1/OSC=>_6") (pintype "bidirectional"))
    )
    (net (code "62") (name "Net-(STM32F103RET6J-BOOT0)") (class "Default")
      (node (ref "R8") (pin "1") (pinfunction "1_1") (pintype "passive"))
      (node (ref "STM32F103RET6") (pin "60") (pinfunction "BOOT0_60") (pintype "input"))
    )
    (net (code "63") (name "Net-(STM32F103RET6J-NRST)") (class "Default")
      (node (ref "R9") (pin "2") (pinfunction "2_2") (pintype "passive"))
      (node (ref "STM32F103RET6") (pin "7") (pinfunction "NRST_7") (pintype "input"))
    )
    (net (code "64") (name "SPI1_MISO") (class "Default")
      (node (ref "NRF24L01_SMD") (pin "P$3") (pinfunction "MISO_P$3") (pintype "output"))
      (node (ref "STM32F103RET6") (pin "22") (pinfunction "PA6_22") (pintype "bidirectional"))
    )
    (net (code "65") (name "SPI1_MOSI") (class "Default")
      (node (ref "NRF24L01_SMD") (pin "P$4") (pinfunction "MOSI_P$4") (pintype "input"))
      (node (ref "STM32F103RET6") (pin "23") (pinfunction "PA7_23") (pintype "bidirectional"))
    )
    (net (code "66") (name "SPI1_SCK") (class "Default")
      (node (ref "NRF24L01_SMD") (pin "P$5") (pinfunction "SCK_P$5") (pintype "input"))
      (node (ref "STM32F103RET6") (pin "21") (pinfunction "PA5_21") (pintype "bidirectional"))
    )
    (net (code "67") (name "SPI2_MISO") (class "Default")
      (node (ref "RFM95") (pin "2") (pinfunction "MISO_2") (pintype "output"))
      (node (ref "STM32F103RET6") (pin "35") (pinfunction "PB14_35") (pintype "bidirectional"))
    )
    (net (code "68") (name "SPI2_MOSI") (class "Default")
      (node (ref "RFM95") (pin "3") (pinfunction "MOSI_3") (pintype "input"))
      (node (ref "STM32F103RET6") (pin "36") (pinfunction "PB15_36") (pintype "bidirectional"))
    )
    (net (code "69") (name "SPI2_SCK") (class "Default")
      (node (ref "RFM95") (pin "4") (pinfunction "SCK_4") (pintype "input"))
      (node (ref "STM32F103RET6") (pin "34") (pinfunction "PB13_34") (pintype "bidirectional"))
    )
    (net (code "70") (name "SWCLK") (class "Default")
      (node (ref "D2") (pin "C") (pinfunction "C_C") (pintype "passive"))
      (node (ref "STM32F103RET6") (pin "49") (pinfunction "PA14_49") (pintype "bidirectional"))
      (node (ref "SWD") (pin "2") (pinfunction "2_2") (pintype "passive"))
    )
    (net (code "71") (name "SWDIO") (class "Default")
      (node (ref "D1") (pin "C") (pinfunction "C_C") (pintype "passive"))
      (node (ref "STM32F103RET6") (pin "46") (pinfunction "PA13_46") (pintype "bidirectional"))
      (node (ref "SWD") (pin "4") (pinfunction "4_4") (pintype "passive"))
    )
    (net (code "72") (name "USART1_CK") (class "Default")
      (node (ref "STM32F103RET6") (pin "41") (pinfunction "PA8_41") (pintype "bidirectional"))
    )
    (net (code "73") (name "USART1_RX") (class "Default")
      (node (ref "2N2222_RX") (pin "C") (pinfunction "C_C") (pintype "passive"))
      (node (ref "R17") (pin "2") (pinfunction "2_2") (pintype "passive"))
      (node (ref "STM32F103RET6") (pin "43") (pinfunction "PA10_43") (pintype "bidirectional"))
    )
    (net (code "74") (name "USART1_TX") (class "Default")
      (node (ref "R12") (pin "2") (pinfunction "2_2") (pintype "passive"))
      (node (ref "STM32F103RET6") (pin "42") (pinfunction "PA9_42") (pintype "bidirectional"))
    )
    (net (code "75") (name "USART3_RX") (class "Default")
      (node (ref "STM32F103RET6") (pin "52") (pinfunction "PC11_52") (pintype "bidirectional"))
    )
    (net (code "76") (name "USART3_TX") (class "Default")
      (node (ref "2N2222_TX1") (pin "B") (pinfunction "B_B") (pintype "passive"))
      (node (ref "STM32F103RET6") (pin "51") (pinfunction "PC10_51") (pintype "bidirectional"))
    )
    (net (code "77") (name "V+") (class "Default")
      (node (ref "BAT60JFILM") (pin "A") (pinfunction "A_A") (pintype "passive"))
      (node (ref "C20") (pin "1") (pinfunction "1_1") (pintype "passive"))
      (node (ref "C21") (pin "1") (pinfunction "1_1") (pintype "passive"))
      (node (ref "C22") (pin "1") (pinfunction "1_1") (pintype "passive"))
      (node (ref "C5") (pin "+") (pinfunction "+_+") (pintype "passive"))
      (node (ref "C7") (pin "1") (pinfunction "1_1") (pintype "passive"))
      (node (ref "CH0") (pin "2") (pinfunction "2_2") (pintype "passive"))
      (node (ref "CH1") (pin "2") (pinfunction "2_2") (pintype "passive"))
      (node (ref "CH10") (pin "2") (pinfunction "2_2") (pintype "passive"))
      (node (ref "CH11") (pin "2") (pinfunction "2_2") (pintype "passive"))
      (node (ref "CH2") (pin "2") (pinfunction "2_2") (pintype "passive"))
      (node (ref "CH3") (pin "2") (pinfunction "2_2") (pintype "passive"))
      (node (ref "CH4") (pin "2") (pinfunction "2_2") (pintype "passive"))
      (node (ref "CH5") (pin "2") (pinfunction "2_2") (pintype "passive"))
      (node (ref "CH6") (pin "2") (pinfunction "2_2") (pintype "passive"))
      (node (ref "CH7") (pin "2") (pinfunction "2_2") (pintype "passive"))
      (node (ref "CH8") (pin "2") (pinfunction "2_2") (pintype "passive"))
      (node (ref "CH9") (pin "2") (pinfunction "2_2") (pintype "passive"))
      (node (ref "SBUS") (pin "2") (pinfunction "2_2") (pintype "passive"))
      (node (ref "SPORT") (pin "2") (pinfunction "2_2") (pintype "passive"))
    )
    (net (code "78") (name "VCC") (class "Default")
      (node (ref "C10") (pin "1") (pinfunction "1_1") (pintype "passive"))
      (node (ref "C11") (pin "1") (pinfunction "1_1") (pintype "passive"))
      (node (ref "C12") (pin "1") (pinfunction "1_1") (pintype "passive"))
      (node (ref "C13") (pin "1") (pinfunction "1_1") (pintype "passive"))
      (node (ref "C14") (pin "1") (pinfunction "1_1") (pintype "passive"))
      (node (ref "C15") (pin "1") (pinfunction "1_1") (pintype "passive"))
      (node (ref "C16") (pin "1") (pinfunction "1_1") (pintype "passive"))
      (node (ref "C17") (pin "1") (pinfunction "1_1") (pintype "passive"))
      (node (ref "C18") (pin "1") (pinfunction "1_1") (pintype "passive"))
      (node (ref "C25") (pin "1") (pinfunction "1_1") (pintype "passive"))
      (node (ref "C3") (pin "1") (pinfunction "1_1") (pintype "passive"))
      (node (ref "C4") (pin "2") (pinfunction "2_2") (pintype "passive"))
      (node (ref "C6") (pin "1") (pinfunction "1_1") (pintype "passive"))
      (node (ref "FCM1608-0603") (pin "1") (pinfunction "P$1_1") (pintype "bidirectional"))
      (node (ref "IC1") (pin "2") (pinfunction "VOUT_2") (pintype "power_in"))
      (node (ref "IC1") (pin "4") (pinfunction "VOUT_4") (pintype "power_in"))
      (node (ref "MPU9150") (pin "13") (pinfunction "VDD_13") (pintype "bidirectional"))
      (node (ref "MPU9150") (pin "3") (pinfunction "VDD_3") (pintype "bidirectional"))
      (node (ref "MPU9150") (pin "8") (pinfunction "VLOGIC_8") (pintype "bidirectional"))
      (node (ref "MS5611") (pin "1") (pinfunction "VDD_1") (pintype "power_in"))
      (node (ref "MS5611") (pin "2") (pinfunction "PS_2") (pintype "input"))
      (node (ref "NRF24L01_SMD") (pin "P$8") (pinfunction "VDD_P$8") (pintype "bidirectional"))
      (node (ref "R10") (pin "1") (pinfunction "1_1") (pintype "passive"))
      (node (ref "R11") (pin "2") (pinfunction "2_2") (pintype "passive"))
      (node (ref "R17") (pin "1") (pinfunction "1_1") (pintype "passive"))
      (node (ref "R18") (pin "1") (pinfunction "1_1") (pintype "passive"))
      (node (ref "R20") (pin "2") (pinfunction "2_2") (pintype "passive"))
      (node (ref "R22") (pin "1") (pinfunction "1_1") (pintype "passive"))
      (node (ref "R3") (pin "1") (pinfunction "1_1") (pintype "passive"))
      (node (ref "R39") (pin "1") (pinfunction "1_1") (pintype "passive"))
      (node (ref "R40") (pin "2") (pinfunction "2_2") (pintype "passive"))
      (node (ref "R9") (pin "1") (pinfunction "1_1") (pintype "passive"))
      (node (ref "RFM95") (pin "13") (pinfunction "VCC_13") (pintype "bidirectional"))
      (node (ref "STM32F103RET6") (pin "1") (pinfunction "VBAT_1") (pintype "power_in"))
      (node (ref "STM32F103RET6") (pin "19") (pinfunction "VDD_4_19") (pintype "power_in"))
      (node (ref "STM32F103RET6") (pin "32") (pinfunction "VDD_1_32") (pintype "power_in"))
      (node (ref "STM32F103RET6") (pin "48") (pinfunction "VDD_2_48") (pintype "power_in"))
      (node (ref "STM32F103RET6") (pin "64") (pinfunction "VDD_3_64") (pintype "power_in"))
      (node (ref "SWD") (pin "1") (pinfunction "1_1") (pintype "passive"))
    )
    (net (code "79") (name "VDD") (class "Default")
      (node (ref "BAT60JFILM") (pin "C") (pinfunction "C_C") (pintype "passive"))
      (node (ref "IC1") (pin "3") (pinfunction "VIN_3") (pintype "input"))
    )
    (net (code "80") (name "unconnected-(MPU9150-CLKOUT-Pad22)") (class "Default")
      (node (ref "MPU9150") (pin "22") (pinfunction "CLKOUT_22") (pintype "bidirectional"))
    )
    (net (code "81") (name "unconnected-(MS5611-SDO-Pad6)") (class "Default")
      (node (ref "MS5611") (pin "6") (pinfunction "SDO_6") (pintype "output"))
    )
    (net (code "82") (name "unconnected-(STM32F103RET6C-PA4-Pad20)") (class "Default")
      (node (ref "STM32F103RET6") (pin "20") (pinfunction "PA4_20") (pintype "bidirectional"))
    )
    (net (code "83") (name "unconnected-(STM32F103RET6E-PB3-Pad55)") (class "Default")
      (node (ref "STM32F103RET6") (pin "55") (pinfunction "PB3_55") (pintype "bidirectional"))
    )
    (net (code "84") (name "unconnected-(STM32F103RET6F-PC13-Pad2)") (class "Default")
      (node (ref "STM32F103RET6") (pin "2") (pinfunction "PC13_2") (pintype "bidirectional"))
    )
    (net (code "85") (name "unconnected-(STM32F103RET6F-PC14-Pad3)") (class "Default")
      (node (ref "STM32F103RET6") (pin "3") (pinfunction "PC14_3") (pintype "bidirectional"))
    )
    (net (code "86") (name "unconnected-(STM32F103RET6F-PC15-Pad4)") (class "Default")
      (node (ref "STM32F103RET6") (pin "4") (pinfunction "PC15_4") (pintype "bidirectional"))
    )
    (net (code "87") (name "unconnected-(STM32F103RET6H-PD2-Pad54)") (class "Default")
      (node (ref "STM32F103RET6") (pin "54") (pinfunction "PD2_54") (pintype "bidirectional"))
    )
  )
)
